# pp_module_jack_rev_b.net
KiCad netlist of a schematic drawn in EAGLE
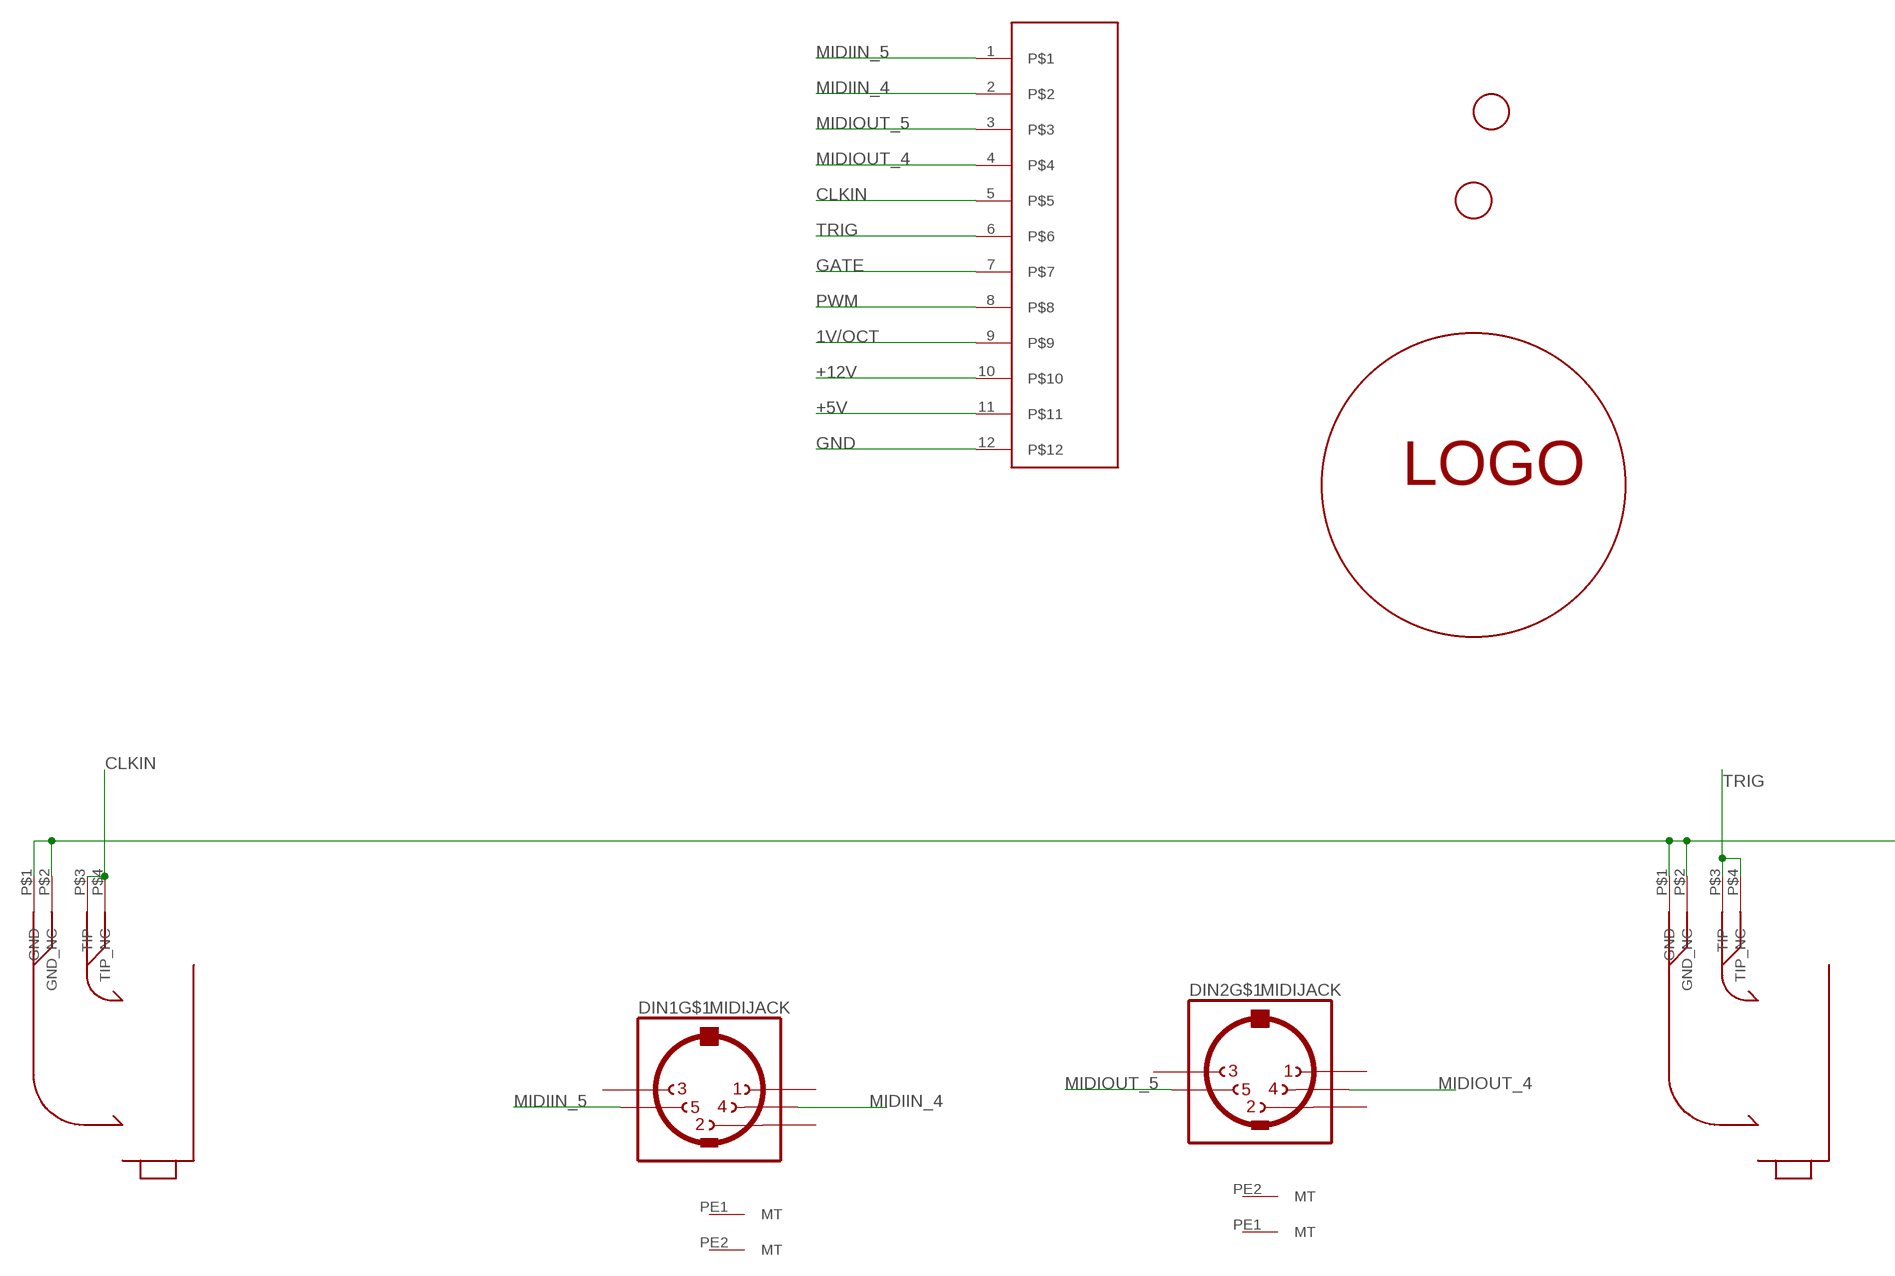
[diagram p0: schematic, sheet 1, part 1 of 2]
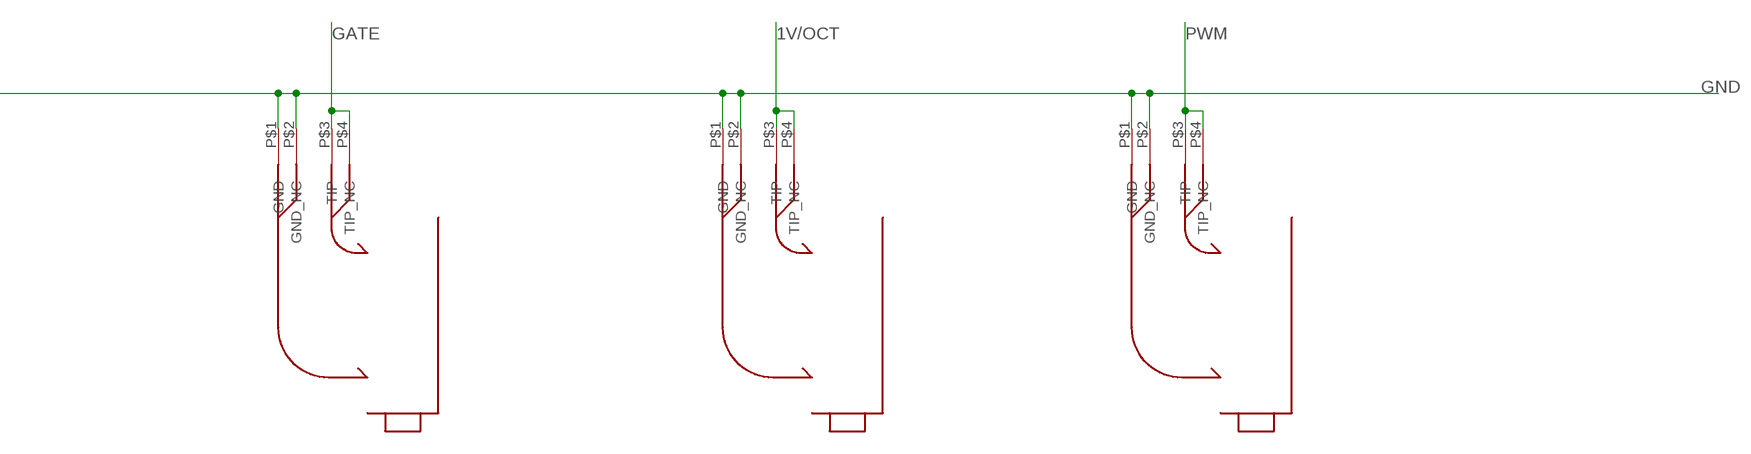
[diagram p1: schematic, sheet 1, part 2 of 2]

(export (version "E")
  (design (tool "Eeschema 10.0.6"))
  (components
    (comp (ref "DIN1")
      (value "MIDIJACK")
      (footprint "eagle-import:CP-2350")
      (fields (field (name "CID") "172"))
      (libsource (lib "eagle-import") (part "MIDIJACK"))
    )
    (comp (ref "DIN2")
      (value "MIDIJACK")
      (footprint "eagle-import:CP-2350")
      (fields (field (name "CID") "172"))
      (libsource (lib "eagle-import") (part "MIDIJACK"))
    )
    (comp (ref "J1")
      (value "MONO_JACKCLIFF")
      (footprint "eagle-import:CLIFF_JACK")
      (libsource (lib "eagle-import") (part "MONO_JACKCLIFF"))
    )
    (comp (ref "J2")
      (value "MONO_JACKCLIFF")
      (footprint "eagle-import:CLIFF_JACK")
      (libsource (lib "eagle-import") (part "MONO_JACKCLIFF"))
    )
    (comp (ref "J3")
      (value "MONO_JACKCLIFF")
      (footprint "eagle-import:CLIFF_JACK")
      (libsource (lib "eagle-import") (part "MONO_JACKCLIFF"))
    )
    (comp (ref "J4")
      (value "MONO_JACKCLIFF")
      (footprint "eagle-import:CLIFF_JACK")
      (libsource (lib "eagle-import") (part "MONO_JACKCLIFF"))
    )
    (comp (ref "J5")
      (value "MONO_JACKCLIFF")
      (footprint "eagle-import:CLIFF_JACK")
      (libsource (lib "eagle-import") (part "MONO_JACKCLIFF"))
    )
    (comp (ref "SOCKET_1")
      (value "CARDEDGE_12POS_SOCKET")
      (footprint "eagle-import:CARDEDGE_12POS_SOCKET")
      (libsource (lib "eagle-import") (part "CARDEDGE_12POS_SOCKET"))
    )
    (comp (ref "U$1")
      (value "FIDUCIAL")
      (footprint "eagle-import:FIDUCIAL_1MM")
      (libsource (lib "eagle-import") (part "FIDUCIAL"))
    )
    (comp (ref "U$2")
      (value "FIDUCIAL")
      (footprint "eagle-import:FIDUCIAL_1MM")
      (libsource (lib "eagle-import") (part "FIDUCIAL"))
    )
    (comp (ref "U$10")
      (value "LOGOCG")
      (footprint "eagle-import:LOGO-CG")
      (libsource (lib "eagle-import") (part "LOGOCG"))
    )
  )
  (nets
    (net (code "1") (name "/+5V") (class "Default")
      (node (ref "SOCKET_1") (pin "11") (pinfunction "P$11_11") (pintype "bidirectional"))
    )
    (net (code "2") (name "/+12V") (class "Default")
      (node (ref "SOCKET_1") (pin "10") (pinfunction "P$10_10") (pintype "bidirectional"))
    )
    (net (code "3") (name "/1V{slash}OCT") (class "Default")
      (node (ref "J4") (pin "P$3") (pinfunction "TIP_P$3") (pintype "bidirectional"))
      (node (ref "J4") (pin "P$4") (pinfunction "TIP_NC_P$4") (pintype "bidirectional"))
      (node (ref "SOCKET_1") (pin "9") (pinfunction "P$9_9") (pintype "bidirectional"))
    )
    (net (code "4") (name "/CLKIN") (class "Default")
      (node (ref "J1") (pin "P$3") (pinfunction "TIP_P$3") (pintype "bidirectional"))
      (node (ref "J1") (pin "P$4") (pinfunction "TIP_NC_P$4") (pintype "bidirectional"))
      (node (ref "SOCKET_1") (pin "5") (pinfunction "P$5_5") (pintype "bidirectional"))
    )
    (net (code "5") (name "/GATE") (class "Default")
      (node (ref "J3") (pin "P$3") (pinfunction "TIP_P$3") (pintype "bidirectional"))
      (node (ref "J3") (pin "P$4") (pinfunction "TIP_NC_P$4") (pintype "bidirectional"))
      (node (ref "SOCKET_1") (pin "7") (pinfunction "P$7_7") (pintype "bidirectional"))
    )
    (net (code "6") (name "/GND") (class "Default")
      (node (ref "J1") (pin "P$1") (pinfunction "GND_P$1") (pintype "bidirectional"))
      (node (ref "J1") (pin "P$2") (pinfunction "GND_NC_P$2") (pintype "bidirectional"))
      (node (ref "J2") (pin "P$1") (pinfunction "GND_P$1") (pintype "bidirectional"))
      (node (ref "J2") (pin "P$2") (pinfunction "GND_NC_P$2") (pintype "bidirectional"))
      (node (ref "J3") (pin "P$1") (pinfunction "GND_P$1") (pintype "bidirectional"))
      (node (ref "J3") (pin "P$2") (pinfunction "GND_NC_P$2") (pintype "bidirectional"))
      (node (ref "J4") (pin "P$1") (pinfunction "GND_P$1") (pintype "bidirectional"))
      (node (ref "J4") (pin "P$2") (pinfunction "GND_NC_P$2") (pintype "bidirectional"))
      (node (ref "J5") (pin "P$1") (pinfunction "GND_P$1") (pintype "bidirectional"))
      (node (ref "J5") (pin "P$2") (pinfunction "GND_NC_P$2") (pintype "bidirectional"))
      (node (ref "SOCKET_1") (pin "12") (pinfunction "P$12_12") (pintype "bidirectional"))
    )
    (net (code "7") (name "/MIDIIN_4") (class "Default")
      (node (ref "DIN1") (pin "4") (pinfunction "4_4") (pintype "passive"))
      (node (ref "SOCKET_1") (pin "2") (pinfunction "P$2_2") (pintype "bidirectional"))
    )
    (net (code "8") (name "/MIDIIN_5") (class "Default")
      (node (ref "DIN1") (pin "5") (pinfunction "5_5") (pintype "passive"))
      (node (ref "SOCKET_1") (pin "1") (pinfunction "P$1_1") (pintype "bidirectional"))
    )
    (net (code "9") (name "/MIDIOUT_4") (class "Default")
      (node (ref "DIN2") (pin "4") (pinfunction "4_4") (pintype "passive"))
      (node (ref "SOCKET_1") (pin "4") (pinfunction "P$4_4") (pintype "bidirectional"))
    )
    (net (code "10") (name "/MIDIOUT_5") (class "Default")
      (node (ref "DIN2") (pin "5") (pinfunction "5_5") (pintype "passive"))
      (node (ref "SOCKET_1") (pin "3") (pinfunction "P$3_3") (pintype "bidirectional"))
    )
    (net (code "11") (name "/PWM") (class "Default")
      (node (ref "J5") (pin "P$3") (pinfunction "TIP_P$3") (pintype "bidirectional"))
      (node (ref "J5") (pin "P$4") (pinfunction "TIP_NC_P$4") (pintype "bidirectional"))
      (node (ref "SOCKET_1") (pin "8") (pinfunction "P$8_8") (pintype "bidirectional"))
    )
    (net (code "12") (name "/TRIG") (class "Default")
      (node (ref "J2") (pin "P$3") (pinfunction "TIP_P$3") (pintype "bidirectional"))
      (node (ref "J2") (pin "P$4") (pinfunction "TIP_NC_P$4") (pintype "bidirectional"))
      (node (ref "SOCKET_1") (pin "6") (pinfunction "P$6_6") (pintype "bidirectional"))
    )
    (net (code "13") (name "unconnected-(DIN1-Pad1)") (class "Default")
      (node (ref "DIN1") (pin "1") (pinfunction "1_1") (pintype "passive"))
    )
    (net (code "14") (name "unconnected-(DIN1-Pad2)") (class "Default")
      (node (ref "DIN1") (pin "2") (pinfunction "2_2") (pintype "passive"))
    )
    (net (code "15") (name "unconnected-(DIN1-Pad3)") (class "Default")
      (node (ref "DIN1") (pin "3") (pinfunction "3_3") (pintype "passive"))
    )
    (net (code "16") (name "unconnected-(DIN1D-MT-PadPE1)") (class "Default")
      (node (ref "DIN1") (pin "PE1") (pinfunction "MT_PE1") (pintype "passive"))
    )
    (net (code "17") (name "unconnected-(DIN1E-MT-PadPE2)") (class "Default")
      (node (ref "DIN1") (pin "PE2") (pinfunction "MT_PE2") (pintype "passive"))
    )
    (net (code "18") (name "unconnected-(DIN2-Pad1)") (class "Default")
      (node (ref "DIN2") (pin "1") (pinfunction "1_1") (pintype "passive"))
    )
    (net (code "19") (name "unconnected-(DIN2-Pad2)") (class "Default")
      (node (ref "DIN2") (pin "2") (pinfunction "2_2") (pintype "passive"))
    )
    (net (code "20") (name "unconnected-(DIN2-Pad3)") (class "Default")
      (node (ref "DIN2") (pin "3") (pinfunction "3_3") (pintype "passive"))
    )
    (net (code "21") (name "unconnected-(DIN2D-MT-PadPE1)") (class "Default")
      (node (ref "DIN2") (pin "PE1") (pinfunction "MT_PE1") (pintype "passive"))
    )
    (net (code "22") (name "unconnected-(DIN2E-MT-PadPE2)") (class "Default")
      (node (ref "DIN2") (pin "PE2") (pinfunction "MT_PE2") (pintype "passive"))
    )
  )
)
